# JacdacBreadboardEc30-16x6_128.net
KiCad netlist of a schematic drawn in Altium Designer
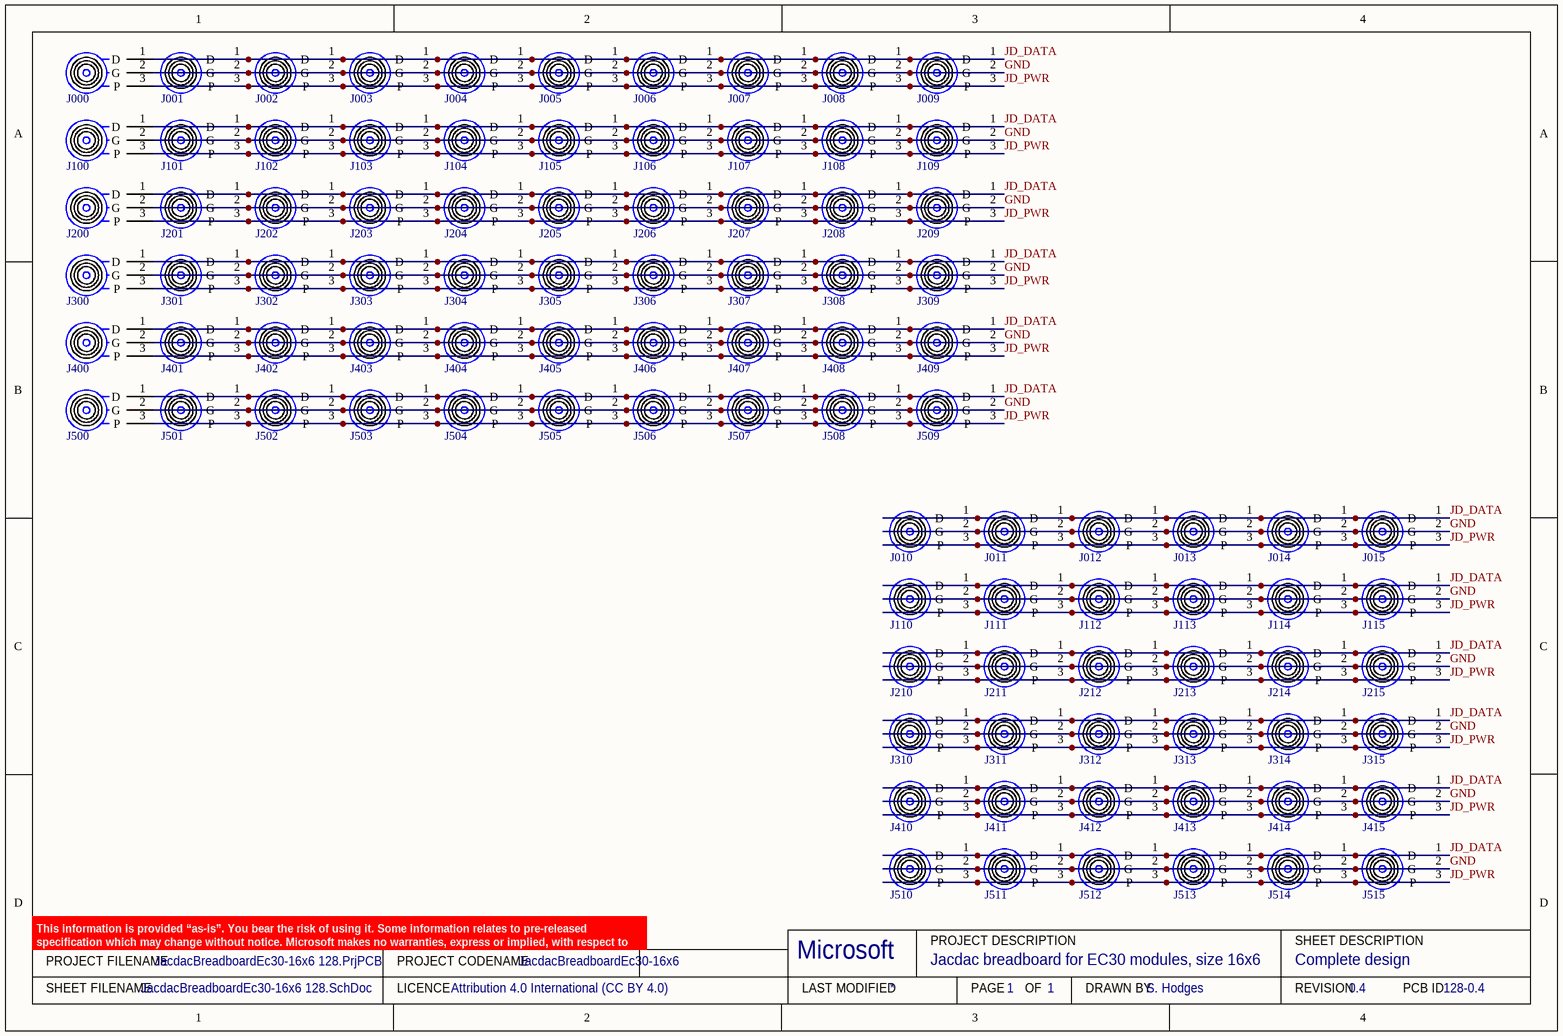
[diagram p0: JacdacBreadboardEc30-16x6 128.SchDoc]

(export (version "E")
  (design (tool "Eeschema 10.0.6"))
  (components
    (comp (ref "J000")
      (value "Jacdac breadboard MH rings")
      (footprint "Jacdac_misc:Jacdac_breadboard_MH_rings_alternative_v5")
      (libsource (lib "generic-con") (part "Jacdac breadboard MH rings"))
    )
    (comp (ref "J001")
      (value "Jacdac breadboard MH rings")
      (footprint "Jacdac_misc:Jacdac_breadboard_MH_rings_alternative_v5")
      (libsource (lib "generic-con") (part "Jacdac breadboard MH rings"))
    )
    (comp (ref "J002")
      (value "Jacdac breadboard MH rings")
      (footprint "Jacdac_misc:Jacdac_breadboard_MH_rings_alternative_v5")
      (libsource (lib "generic-con") (part "Jacdac breadboard MH rings"))
    )
    (comp (ref "J003")
      (value "Jacdac breadboard MH rings")
      (footprint "Jacdac_misc:Jacdac_breadboard_MH_rings_alternative_v5")
      (libsource (lib "generic-con") (part "Jacdac breadboard MH rings"))
    )
    (comp (ref "J004")
      (value "Jacdac breadboard MH rings")
      (footprint "Jacdac_misc:Jacdac_breadboard_MH_rings_alternative_v5")
      (libsource (lib "generic-con") (part "Jacdac breadboard MH rings"))
    )
    (comp (ref "J005")
      (value "Jacdac breadboard MH rings")
      (footprint "Jacdac_misc:Jacdac_breadboard_MH_rings_alternative_v5")
      (libsource (lib "generic-con") (part "Jacdac breadboard MH rings"))
    )
    (comp (ref "J006")
      (value "Jacdac breadboard MH rings")
      (footprint "Jacdac_misc:Jacdac_breadboard_MH_rings_alternative_v5")
      (libsource (lib "generic-con") (part "Jacdac breadboard MH rings"))
    )
    (comp (ref "J007")
      (value "Jacdac breadboard MH rings")
      (footprint "Jacdac_misc:Jacdac_breadboard_MH_rings_alternative_v5")
      (libsource (lib "generic-con") (part "Jacdac breadboard MH rings"))
    )
    (comp (ref "J008")
      (value "Jacdac breadboard MH rings")
      (footprint "Jacdac_misc:Jacdac_breadboard_MH_rings_alternative_v5")
      (libsource (lib "generic-con") (part "Jacdac breadboard MH rings"))
    )
    (comp (ref "J009")
      (value "Jacdac breadboard MH rings")
      (footprint "Jacdac_misc:Jacdac_breadboard_MH_rings_alternative_v5")
      (libsource (lib "generic-con") (part "Jacdac breadboard MH rings"))
    )
    (comp (ref "J010")
      (value "Jacdac breadboard MH rings")
      (footprint "Jacdac_misc:Jacdac_breadboard_MH_rings_alternative_v5")
      (libsource (lib "generic-con") (part "Jacdac breadboard MH rings"))
    )
    (comp (ref "J011")
      (value "Jacdac breadboard MH rings")
      (footprint "Jacdac_misc:Jacdac_breadboard_MH_rings_alternative_v5")
      (libsource (lib "generic-con") (part "Jacdac breadboard MH rings"))
    )
    (comp (ref "J012")
      (value "Jacdac breadboard MH rings")
      (footprint "Jacdac_misc:Jacdac_breadboard_MH_rings_alternative_v5")
      (libsource (lib "generic-con") (part "Jacdac breadboard MH rings"))
    )
    (comp (ref "J013")
      (value "Jacdac breadboard MH rings")
      (footprint "Jacdac_misc:Jacdac_breadboard_MH_rings_alternative_v5")
      (libsource (lib "generic-con") (part "Jacdac breadboard MH rings"))
    )
    (comp (ref "J014")
      (value "Jacdac breadboard MH rings")
      (footprint "Jacdac_misc:Jacdac_breadboard_MH_rings_alternative_v5")
      (libsource (lib "generic-con") (part "Jacdac breadboard MH rings"))
    )
    (comp (ref "J015")
      (value "Jacdac breadboard MH rings")
      (footprint "Jacdac_misc:Jacdac_breadboard_MH_rings_alternative_v5")
      (libsource (lib "generic-con") (part "Jacdac breadboard MH rings"))
    )
    (comp (ref "J100")
      (value "Jacdac breadboard MH rings")
      (footprint "Jacdac_misc:Jacdac_breadboard_MH_rings_alternative_v5")
      (libsource (lib "generic-con") (part "Jacdac breadboard MH rings"))
    )
    (comp (ref "J101")
      (value "Jacdac breadboard MH rings")
      (footprint "Jacdac_misc:Jacdac_breadboard_MH_rings_alternative_v5")
      (libsource (lib "generic-con") (part "Jacdac breadboard MH rings"))
    )
    (comp (ref "J102")
      (value "Jacdac breadboard MH rings")
      (footprint "Jacdac_misc:Jacdac_breadboard_MH_rings_alternative_v5")
      (libsource (lib "generic-con") (part "Jacdac breadboard MH rings"))
    )
    (comp (ref "J103")
      (value "Jacdac breadboard MH rings")
      (footprint "Jacdac_misc:Jacdac_breadboard_MH_rings_alternative_v5")
      (libsource (lib "generic-con") (part "Jacdac breadboard MH rings"))
    )
    (comp (ref "J104")
      (value "Jacdac breadboard MH rings")
      (footprint "Jacdac_misc:Jacdac_breadboard_MH_rings_alternative_v5")
      (libsource (lib "generic-con") (part "Jacdac breadboard MH rings"))
    )
    (comp (ref "J105")
      (value "Jacdac breadboard MH rings")
      (footprint "Jacdac_misc:Jacdac_breadboard_MH_rings_alternative_v5")
      (libsource (lib "generic-con") (part "Jacdac breadboard MH rings"))
    )
    (comp (ref "J106")
      (value "Jacdac breadboard MH rings")
      (footprint "Jacdac_misc:Jacdac_breadboard_MH_rings_alternative_v5")
      (libsource (lib "generic-con") (part "Jacdac breadboard MH rings"))
    )
    (comp (ref "J107")
      (value "Jacdac breadboard MH rings")
      (footprint "Jacdac_misc:Jacdac_breadboard_MH_rings_alternative_v5")
      (libsource (lib "generic-con") (part "Jacdac breadboard MH rings"))
    )
    (comp (ref "J108")
      (value "Jacdac breadboard MH rings")
      (footprint "Jacdac_misc:Jacdac_breadboard_MH_rings_alternative_v5")
      (libsource (lib "generic-con") (part "Jacdac breadboard MH rings"))
    )
    (comp (ref "J109")
      (value "Jacdac breadboard MH rings")
      (footprint "Jacdac_misc:Jacdac_breadboard_MH_rings_alternative_v5")
      (libsource (lib "generic-con") (part "Jacdac breadboard MH rings"))
    )
    (comp (ref "J110")
      (value "Jacdac breadboard MH rings")
      (footprint "Jacdac_misc:Jacdac_breadboard_MH_rings_alternative_v5")
      (libsource (lib "generic-con") (part "Jacdac breadboard MH rings"))
    )
    (comp (ref "J111")
      (value "Jacdac breadboard MH rings")
      (footprint "Jacdac_misc:Jacdac_breadboard_MH_rings_alternative_v5")
      (libsource (lib "generic-con") (part "Jacdac breadboard MH rings"))
    )
    (comp (ref "J112")
      (value "Jacdac breadboard MH rings")
      (footprint "Jacdac_misc:Jacdac_breadboard_MH_rings_alternative_v5")
      (libsource (lib "generic-con") (part "Jacdac breadboard MH rings"))
    )
    (comp (ref "J113")
      (value "Jacdac breadboard MH rings")
      (footprint "Jacdac_misc:Jacdac_breadboard_MH_rings_alternative_v5")
      (libsource (lib "generic-con") (part "Jacdac breadboard MH rings"))
    )
    (comp (ref "J114")
      (value "Jacdac breadboard MH rings")
      (footprint "Jacdac_misc:Jacdac_breadboard_MH_rings_alternative_v5")
      (libsource (lib "generic-con") (part "Jacdac breadboard MH rings"))
    )
    (comp (ref "J115")
      (value "Jacdac breadboard MH rings")
      (footprint "Jacdac_misc:Jacdac_breadboard_MH_rings_alternative_v5")
      (libsource (lib "generic-con") (part "Jacdac breadboard MH rings"))
    )
    (comp (ref "J200")
      (value "Jacdac breadboard MH rings")
      (footprint "Jacdac_misc:Jacdac_breadboard_MH_rings_alternative_v5")
      (libsource (lib "generic-con") (part "Jacdac breadboard MH rings"))
    )
    (comp (ref "J201")
      (value "Jacdac breadboard MH rings")
      (footprint "Jacdac_misc:Jacdac_breadboard_MH_rings_alternative_v5")
      (libsource (lib "generic-con") (part "Jacdac breadboard MH rings"))
    )
    (comp (ref "J202")
      (value "Jacdac breadboard MH rings")
      (footprint "Jacdac_misc:Jacdac_breadboard_MH_rings_alternative_v5")
      (libsource (lib "generic-con") (part "Jacdac breadboard MH rings"))
    )
    (comp (ref "J203")
      (value "Jacdac breadboard MH rings")
      (footprint "Jacdac_misc:Jacdac_breadboard_MH_rings_alternative_v5")
      (libsource (lib "generic-con") (part "Jacdac breadboard MH rings"))
    )
    (comp (ref "J204")
      (value "Jacdac breadboard MH rings")
      (footprint "Jacdac_misc:Jacdac_breadboard_MH_rings_alternative_v5")
      (libsource (lib "generic-con") (part "Jacdac breadboard MH rings"))
    )
    (comp (ref "J205")
      (value "Jacdac breadboard MH rings")
      (footprint "Jacdac_misc:Jacdac_breadboard_MH_rings_alternative_v5")
      (libsource (lib "generic-con") (part "Jacdac breadboard MH rings"))
    )
    (comp (ref "J206")
      (value "Jacdac breadboard MH rings")
      (footprint "Jacdac_misc:Jacdac_breadboard_MH_rings_alternative_v5")
      (libsource (lib "generic-con") (part "Jacdac breadboard MH rings"))
    )
    (comp (ref "J207")
      (value "Jacdac breadboard MH rings")
      (footprint "Jacdac_misc:Jacdac_breadboard_MH_rings_alternative_v5")
      (libsource (lib "generic-con") (part "Jacdac breadboard MH rings"))
    )
    (comp (ref "J208")
      (value "Jacdac breadboard MH rings")
      (footprint "Jacdac_misc:Jacdac_breadboard_MH_rings_alternative_v5")
      (libsource (lib "generic-con") (part "Jacdac breadboard MH rings"))
    )
    (comp (ref "J209")
      (value "Jacdac breadboard MH rings")
      (footprint "Jacdac_misc:Jacdac_breadboard_MH_rings_alternative_v5")
      (libsource (lib "generic-con") (part "Jacdac breadboard MH rings"))
    )
    (comp (ref "J210")
      (value "Jacdac breadboard MH rings")
      (footprint "Jacdac_misc:Jacdac_breadboard_MH_rings_alternative_v5")
      (libsource (lib "generic-con") (part "Jacdac breadboard MH rings"))
    )
    (comp (ref "J211")
      (value "Jacdac breadboard MH rings")
      (footprint "Jacdac_misc:Jacdac_breadboard_MH_rings_alternative_v5")
      (libsource (lib "generic-con") (part "Jacdac breadboard MH rings"))
    )
    (comp (ref "J212")
      (value "Jacdac breadboard MH rings")
      (footprint "Jacdac_misc:Jacdac_breadboard_MH_rings_alternative_v5")
      (libsource (lib "generic-con") (part "Jacdac breadboard MH rings"))
    )
    (comp (ref "J213")
      (value "Jacdac breadboard MH rings")
      (footprint "Jacdac_misc:Jacdac_breadboard_MH_rings_alternative_v5")
      (libsource (lib "generic-con") (part "Jacdac breadboard MH rings"))
    )
    (comp (ref "J214")
      (value "Jacdac breadboard MH rings")
      (footprint "Jacdac_misc:Jacdac_breadboard_MH_rings_alternative_v5")
      (libsource (lib "generic-con") (part "Jacdac breadboard MH rings"))
    )
    (comp (ref "J215")
      (value "Jacdac breadboard MH rings")
      (footprint "Jacdac_misc:Jacdac_breadboard_MH_rings_alternative_v5")
      (libsource (lib "generic-con") (part "Jacdac breadboard MH rings"))
    )
    (comp (ref "J300")
      (value "Jacdac breadboard MH rings")
      (footprint "Jacdac_misc:Jacdac_breadboard_MH_rings_alternative_v5")
      (libsource (lib "generic-con") (part "Jacdac breadboard MH rings"))
    )
    (comp (ref "J301")
      (value "Jacdac breadboard MH rings")
      (footprint "Jacdac_misc:Jacdac_breadboard_MH_rings_alternative_v5")
      (libsource (lib "generic-con") (part "Jacdac breadboard MH rings"))
    )
    (comp (ref "J302")
      (value "Jacdac breadboard MH rings")
      (footprint "Jacdac_misc:Jacdac_breadboard_MH_rings_alternative_v5")
      (libsource (lib "generic-con") (part "Jacdac breadboard MH rings"))
    )
    (comp (ref "J303")
      (value "Jacdac breadboard MH rings")
      (footprint "Jacdac_misc:Jacdac_breadboard_MH_rings_alternative_v5")
      (libsource (lib "generic-con") (part "Jacdac breadboard MH rings"))
    )
    (comp (ref "J304")
      (value "Jacdac breadboard MH rings")
      (footprint "Jacdac_misc:Jacdac_breadboard_MH_rings_alternative_v5")
      (libsource (lib "generic-con") (part "Jacdac breadboard MH rings"))
    )
    (comp (ref "J305")
      (value "Jacdac breadboard MH rings")
      (footprint "Jacdac_misc:Jacdac_breadboard_MH_rings_alternative_v5")
      (libsource (lib "generic-con") (part "Jacdac breadboard MH rings"))
    )
    (comp (ref "J306")
      (value "Jacdac breadboard MH rings")
      (footprint "Jacdac_misc:Jacdac_breadboard_MH_rings_alternative_v5")
      (libsource (lib "generic-con") (part "Jacdac breadboard MH rings"))
    )
    (comp (ref "J307")
      (value "Jacdac breadboard MH rings")
      (footprint "Jacdac_misc:Jacdac_breadboard_MH_rings_alternative_v5")
      (libsource (lib "generic-con") (part "Jacdac breadboard MH rings"))
    )
    (comp (ref "J308")
      (value "Jacdac breadboard MH rings")
      (footprint "Jacdac_misc:Jacdac_breadboard_MH_rings_alternative_v5")
      (libsource (lib "generic-con") (part "Jacdac breadboard MH rings"))
    )
    (comp (ref "J309")
      (value "Jacdac breadboard MH rings")
      (footprint "Jacdac_misc:Jacdac_breadboard_MH_rings_alternative_v5")
      (libsource (lib "generic-con") (part "Jacdac breadboard MH rings"))
    )
    (comp (ref "J310")
      (value "Jacdac breadboard MH rings")
      (footprint "Jacdac_misc:Jacdac_breadboard_MH_rings_alternative_v5")
      (libsource (lib "generic-con") (part "Jacdac breadboard MH rings"))
    )
    (comp (ref "J311")
      (value "Jacdac breadboard MH rings")
      (footprint "Jacdac_misc:Jacdac_breadboard_MH_rings_alternative_v5")
      (libsource (lib "generic-con") (part "Jacdac breadboard MH rings"))
    )
    (comp (ref "J312")
      (value "Jacdac breadboard MH rings")
      (footprint "Jacdac_misc:Jacdac_breadboard_MH_rings_alternative_v5")
      (libsource (lib "generic-con") (part "Jacdac breadboard MH rings"))
    )
    (comp (ref "J313")
      (value "Jacdac breadboard MH rings")
      (footprint "Jacdac_misc:Jacdac_breadboard_MH_rings_alternative_v5")
      (libsource (lib "generic-con") (part "Jacdac breadboard MH rings"))
    )
    (comp (ref "J314")
      (value "Jacdac breadboard MH rings")
      (footprint "Jacdac_misc:Jacdac_breadboard_MH_rings_alternative_v5")
      (libsource (lib "generic-con") (part "Jacdac breadboard MH rings"))
    )
    (comp (ref "J315")
      (value "Jacdac breadboard MH rings")
      (footprint "Jacdac_misc:Jacdac_breadboard_MH_rings_alternative_v5")
      (libsource (lib "generic-con") (part "Jacdac breadboard MH rings"))
    )
    (comp (ref "J400")
      (value "Jacdac breadboard MH rings")
      (footprint "Jacdac_misc:Jacdac_breadboard_MH_rings_alternative_v5")
      (libsource (lib "generic-con") (part "Jacdac breadboard MH rings"))
    )
    (comp (ref "J401")
      (value "Jacdac breadboard MH rings")
      (footprint "Jacdac_misc:Jacdac_breadboard_MH_rings_alternative_v5")
      (libsource (lib "generic-con") (part "Jacdac breadboard MH rings"))
    )
    (comp (ref "J402")
      (value "Jacdac breadboard MH rings")
      (footprint "Jacdac_misc:Jacdac_breadboard_MH_rings_alternative_v5")
      (libsource (lib "generic-con") (part "Jacdac breadboard MH rings"))
    )
    (comp (ref "J403")
      (value "Jacdac breadboard MH rings")
      (footprint "Jacdac_misc:Jacdac_breadboard_MH_rings_alternative_v5")
      (libsource (lib "generic-con") (part "Jacdac breadboard MH rings"))
    )
    (comp (ref "J404")
      (value "Jacdac breadboard MH rings")
      (footprint "Jacdac_misc:Jacdac_breadboard_MH_rings_alternative_v5")
      (libsource (lib "generic-con") (part "Jacdac breadboard MH rings"))
    )
    (comp (ref "J405")
      (value "Jacdac breadboard MH rings")
      (footprint "Jacdac_misc:Jacdac_breadboard_MH_rings_alternative_v5")
      (libsource (lib "generic-con") (part "Jacdac breadboard MH rings"))
    )
    (comp (ref "J406")
      (value "Jacdac breadboard MH rings")
      (footprint "Jacdac_misc:Jacdac_breadboard_MH_rings_alternative_v5")
      (libsource (lib "generic-con") (part "Jacdac breadboard MH rings"))
    )
    (comp (ref "J407")
      (value "Jacdac breadboard MH rings")
      (footprint "Jacdac_misc:Jacdac_breadboard_MH_rings_alternative_v5")
      (libsource (lib "generic-con") (part "Jacdac breadboard MH rings"))
    )
    (comp (ref "J408")
      (value "Jacdac breadboard MH rings")
      (footprint "Jacdac_misc:Jacdac_breadboard_MH_rings_alternative_v5")
      (libsource (lib "generic-con") (part "Jacdac breadboard MH rings"))
    )
    (comp (ref "J409")
      (value "Jacdac breadboard MH rings")
      (footprint "Jacdac_misc:Jacdac_breadboard_MH_rings_alternative_v5")
      (libsource (lib "generic-con") (part "Jacdac breadboard MH rings"))
    )
    (comp (ref "J410")
      (value "Jacdac breadboard MH rings")
      (footprint "Jacdac_misc:Jacdac_breadboard_MH_rings_alternative_v5")
      (libsource (lib "generic-con") (part "Jacdac breadboard MH rings"))
    )
    (comp (ref "J411")
      (value "Jacdac breadboard MH rings")
      (footprint "Jacdac_misc:Jacdac_breadboard_MH_rings_alternative_v5")
      (libsource (lib "generic-con") (part "Jacdac breadboard MH rings"))
    )
    (comp (ref "J412")
      (value "Jacdac breadboard MH rings")
      (footprint "Jacdac_misc:Jacdac_breadboard_MH_rings_alternative_v5")
      (libsource (lib "generic-con") (part "Jacdac breadboard MH rings"))
    )
    (comp (ref "J413")
      (value "Jacdac breadboard MH rings")
      (footprint "Jacdac_misc:Jacdac_breadboard_MH_rings_alternative_v5")
      (libsource (lib "generic-con") (part "Jacdac breadboard MH rings"))
    )
    (comp (ref "J414")
      (value "Jacdac breadboard MH rings")
      (footprint "Jacdac_misc:Jacdac_breadboard_MH_rings_alternative_v5")
      (libsource (lib "generic-con") (part "Jacdac breadboard MH rings"))
    )
    (comp (ref "J415")
      (value "Jacdac breadboard MH rings")
      (footprint "Jacdac_misc:Jacdac_breadboard_MH_rings_alternative_v5")
      (libsource (lib "generic-con") (part "Jacdac breadboard MH rings"))
    )
    (comp (ref "J500")
      (value "Jacdac breadboard MH rings")
      (footprint "Jacdac_misc:Jacdac_breadboard_MH_rings_alternative_v5")
      (libsource (lib "generic-con") (part "Jacdac breadboard MH rings"))
    )
    (comp (ref "J501")
      (value "Jacdac breadboard MH rings")
      (footprint "Jacdac_misc:Jacdac_breadboard_MH_rings_alternative_v5")
      (libsource (lib "generic-con") (part "Jacdac breadboard MH rings"))
    )
    (comp (ref "J502")
      (value "Jacdac breadboard MH rings")
      (footprint "Jacdac_misc:Jacdac_breadboard_MH_rings_alternative_v5")
      (libsource (lib "generic-con") (part "Jacdac breadboard MH rings"))
    )
    (comp (ref "J503")
      (value "Jacdac breadboard MH rings")
      (footprint "Jacdac_misc:Jacdac_breadboard_MH_rings_alternative_v5")
      (libsource (lib "generic-con") (part "Jacdac breadboard MH rings"))
    )
    (comp (ref "J504")
      (value "Jacdac breadboard MH rings")
      (footprint "Jacdac_misc:Jacdac_breadboard_MH_rings_alternative_v5")
      (libsource (lib "generic-con") (part "Jacdac breadboard MH rings"))
    )
    (comp (ref "J505")
      (value "Jacdac breadboard MH rings")
      (footprint "Jacdac_misc:Jacdac_breadboard_MH_rings_alternative_v5")
      (libsource (lib "generic-con") (part "Jacdac breadboard MH rings"))
    )
    (comp (ref "J506")
      (value "Jacdac breadboard MH rings")
      (footprint "Jacdac_misc:Jacdac_breadboard_MH_rings_alternative_v5")
      (libsource (lib "generic-con") (part "Jacdac breadboard MH rings"))
    )
    (comp (ref "J507")
      (value "Jacdac breadboard MH rings")
      (footprint "Jacdac_misc:Jacdac_breadboard_MH_rings_alternative_v5")
      (libsource (lib "generic-con") (part "Jacdac breadboard MH rings"))
    )
    (comp (ref "J508")
      (value "Jacdac breadboard MH rings")
      (footprint "Jacdac_misc:Jacdac_breadboard_MH_rings_alternative_v5")
      (libsource (lib "generic-con") (part "Jacdac breadboard MH rings"))
    )
    (comp (ref "J509")
      (value "Jacdac breadboard MH rings")
      (footprint "Jacdac_misc:Jacdac_breadboard_MH_rings_alternative_v5")
      (libsource (lib "generic-con") (part "Jacdac breadboard MH rings"))
    )
    (comp (ref "J510")
      (value "Jacdac breadboard MH rings")
      (footprint "Jacdac_misc:Jacdac_breadboard_MH_rings_alternative_v5")
      (libsource (lib "generic-con") (part "Jacdac breadboard MH rings"))
    )
    (comp (ref "J511")
      (value "Jacdac breadboard MH rings")
      (footprint "Jacdac_misc:Jacdac_breadboard_MH_rings_alternative_v5")
      (libsource (lib "generic-con") (part "Jacdac breadboard MH rings"))
    )
    (comp (ref "J512")
      (value "Jacdac breadboard MH rings")
      (footprint "Jacdac_misc:Jacdac_breadboard_MH_rings_alternative_v5")
      (libsource (lib "generic-con") (part "Jacdac breadboard MH rings"))
    )
    (comp (ref "J513")
      (value "Jacdac breadboard MH rings")
      (footprint "Jacdac_misc:Jacdac_breadboard_MH_rings_alternative_v5")
      (libsource (lib "generic-con") (part "Jacdac breadboard MH rings"))
    )
    (comp (ref "J514")
      (value "Jacdac breadboard MH rings")
      (footprint "Jacdac_misc:Jacdac_breadboard_MH_rings_alternative_v5")
      (libsource (lib "generic-con") (part "Jacdac breadboard MH rings"))
    )
    (comp (ref "J515")
      (value "Jacdac breadboard MH rings")
      (footprint "Jacdac_misc:Jacdac_breadboard_MH_rings_alternative_v5")
      (libsource (lib "generic-con") (part "Jacdac breadboard MH rings"))
    )
  )
  (nets
    (net (code "1") (name "/GND") (class "Default")
      (node (ref "J000") (pin "2") (pinfunction "G_2") (pintype "passive"))
      (node (ref "J001") (pin "2") (pinfunction "G_2") (pintype "passive"))
      (node (ref "J002") (pin "2") (pinfunction "G_2") (pintype "passive"))
      (node (ref "J003") (pin "2") (pinfunction "G_2") (pintype "passive"))
      (node (ref "J004") (pin "2") (pinfunction "G_2") (pintype "passive"))
      (node (ref "J005") (pin "2") (pinfunction "G_2") (pintype "passive"))
      (node (ref "J006") (pin "2") (pinfunction "G_2") (pintype "passive"))
      (node (ref "J007") (pin "2") (pinfunction "G_2") (pintype "passive"))
      (node (ref "J008") (pin "2") (pinfunction "G_2") (pintype "passive"))
      (node (ref "J009") (pin "2") (pinfunction "G_2") (pintype "passive"))
      (node (ref "J010") (pin "2") (pinfunction "G_2") (pintype "passive"))
      (node (ref "J011") (pin "2") (pinfunction "G_2") (pintype "passive"))
      (node (ref "J012") (pin "2") (pinfunction "G_2") (pintype "passive"))
      (node (ref "J013") (pin "2") (pinfunction "G_2") (pintype "passive"))
      (node (ref "J014") (pin "2") (pinfunction "G_2") (pintype "passive"))
      (node (ref "J015") (pin "2") (pinfunction "G_2") (pintype "passive"))
      (node (ref "J100") (pin "2") (pinfunction "G_2") (pintype "passive"))
      (node (ref "J101") (pin "2") (pinfunction "G_2") (pintype "passive"))
      (node (ref "J102") (pin "2") (pinfunction "G_2") (pintype "passive"))
      (node (ref "J103") (pin "2") (pinfunction "G_2") (pintype "passive"))
      (node (ref "J104") (pin "2") (pinfunction "G_2") (pintype "passive"))
      (node (ref "J105") (pin "2") (pinfunction "G_2") (pintype "passive"))
      (node (ref "J106") (pin "2") (pinfunction "G_2") (pintype "passive"))
      (node (ref "J107") (pin "2") (pinfunction "G_2") (pintype "passive"))
      (node (ref "J108") (pin "2") (pinfunction "G_2") (pintype "passive"))
      (node (ref "J109") (pin "2") (pinfunction "G_2") (pintype "passive"))
      (node (ref "J110") (pin "2") (pinfunction "G_2") (pintype "passive"))
      (node (ref "J111") (pin "2") (pinfunction "G_2") (pintype "passive"))
      (node (ref "J112") (pin "2") (pinfunction "G_2") (pintype "passive"))
      (node (ref "J113") (pin "2") (pinfunction "G_2") (pintype "passive"))
      (node (ref "J114") (pin "2") (pinfunction "G_2") (pintype "passive"))
      (node (ref "J115") (pin "2") (pinfunction "G_2") (pintype "passive"))
      (node (ref "J200") (pin "2") (pinfunction "G_2") (pintype "passive"))
      (node (ref "J201") (pin "2") (pinfunction "G_2") (pintype "passive"))
      (node (ref "J202") (pin "2") (pinfunction "G_2") (pintype "passive"))
      (node (ref "J203") (pin "2") (pinfunction "G_2") (pintype "passive"))
      (node (ref "J204") (pin "2") (pinfunction "G_2") (pintype "passive"))
      (node (ref "J205") (pin "2") (pinfunction "G_2") (pintype "passive"))
      (node (ref "J206") (pin "2") (pinfunction "G_2") (pintype "passive"))
      (node (ref "J207") (pin "2") (pinfunction "G_2") (pintype "passive"))
      (node (ref "J208") (pin "2") (pinfunction "G_2") (pintype "passive"))
      (node (ref "J209") (pin "2") (pinfunction "G_2") (pintype "passive"))
      (node (ref "J210") (pin "2") (pinfunction "G_2") (pintype "passive"))
      (node (ref "J211") (pin "2") (pinfunction "G_2") (pintype "passive"))
      (node (ref "J212") (pin "2") (pinfunction "G_2") (pintype "passive"))
      (node (ref "J213") (pin "2") (pinfunction "G_2") (pintype "passive"))
      (node (ref "J214") (pin "2") (pinfunction "G_2") (pintype "passive"))
      (node (ref "J215") (pin "2") (pinfunction "G_2") (pintype "passive"))
      (node (ref "J300") (pin "2") (pinfunction "G_2") (pintype "passive"))
      (node (ref "J301") (pin "2") (pinfunction "G_2") (pintype "passive"))
      (node (ref "J302") (pin "2") (pinfunction "G_2") (pintype "passive"))
      (node (ref "J303") (pin "2") (pinfunction "G_2") (pintype "passive"))
      (node (ref "J304") (pin "2") (pinfunction "G_2") (pintype "passive"))
      (node (ref "J305") (pin "2") (pinfunction "G_2") (pintype "passive"))
      (node (ref "J306") (pin "2") (pinfunction "G_2") (pintype "passive"))
      (node (ref "J307") (pin "2") (pinfunction "G_2") (pintype "passive"))
      (node (ref "J308") (pin "2") (pinfunction "G_2") (pintype "passive"))
      (node (ref "J309") (pin "2") (pinfunction "G_2") (pintype "passive"))
      (node (ref "J310") (pin "2") (pinfunction "G_2") (pintype "passive"))
      (node (ref "J311") (pin "2") (pinfunction "G_2") (pintype "passive"))
      (node (ref "J312") (pin "2") (pinfunction "G_2") (pintype "passive"))
      (node (ref "J313") (pin "2") (pinfunction "G_2") (pintype "passive"))
      (node (ref "J314") (pin "2") (pinfunction "G_2") (pintype "passive"))
      (node (ref "J315") (pin "2") (pinfunction "G_2") (pintype "passive"))
      (node (ref "J400") (pin "2") (pinfunction "G_2") (pintype "passive"))
      (node (ref "J401") (pin "2") (pinfunction "G_2") (pintype "passive"))
      (node (ref "J402") (pin "2") (pinfunction "G_2") (pintype "passive"))
      (node (ref "J403") (pin "2") (pinfunction "G_2") (pintype "passive"))
      (node (ref "J404") (pin "2") (pinfunction "G_2") (pintype "passive"))
      (node (ref "J405") (pin "2") (pinfunction "G_2") (pintype "passive"))
      (node (ref "J406") (pin "2") (pinfunction "G_2") (pintype "passive"))
      (node (ref "J407") (pin "2") (pinfunction "G_2") (pintype "passive"))
      (node (ref "J408") (pin "2") (pinfunction "G_2") (pintype "passive"))
      (node (ref "J409") (pin "2") (pinfunction "G_2") (pintype "passive"))
      (node (ref "J410") (pin "2") (pinfunction "G_2") (pintype "passive"))
      (node (ref "J411") (pin "2") (pinfunction "G_2") (pintype "passive"))
      (node (ref "J412") (pin "2") (pinfunction "G_2") (pintype "passive"))
      (node (ref "J413") (pin "2") (pinfunction "G_2") (pintype "passive"))
      (node (ref "J414") (pin "2") (pinfunction "G_2") (pintype "passive"))
      (node (ref "J415") (pin "2") (pinfunction "G_2") (pintype "passive"))
      (node (ref "J500") (pin "2") (pinfunction "G_2") (pintype "passive"))
      (node (ref "J501") (pin "2") (pinfunction "G_2") (pintype "passive"))
      (node (ref "J502") (pin "2") (pinfunction "G_2") (pintype "passive"))
      (node (ref "J503") (pin "2") (pinfunction "G_2") (pintype "passive"))
      (node (ref "J504") (pin "2") (pinfunction "G_2") (pintype "passive"))
      (node (ref "J505") (pin "2") (pinfunction "G_2") (pintype "passive"))
      (node (ref "J506") (pin "2") (pinfunction "G_2") (pintype "passive"))
      (node (ref "J507") (pin "2") (pinfunction "G_2") (pintype "passive"))
      (node (ref "J508") (pin "2") (pinfunction "G_2") (pintype "passive"))
      (node (ref "J509") (pin "2") (pinfunction "G_2") (pintype "passive"))
      (node (ref "J510") (pin "2") (pinfunction "G_2") (pintype "passive"))
      (node (ref "J511") (pin "2") (pinfunction "G_2") (pintype "passive"))
      (node (ref "J512") (pin "2") (pinfunction "G_2") (pintype "passive"))
      (node (ref "J513") (pin "2") (pinfunction "G_2") (pintype "passive"))
      (node (ref "J514") (pin "2") (pinfunction "G_2") (pintype "passive"))
      (node (ref "J515") (pin "2") (pinfunction "G_2") (pintype "passive"))
    )
    (net (code "2") (name "/JD_DATA") (class "Default")
      (node (ref "J000") (pin "1") (pinfunction "D_1") (pintype "passive"))
      (node (ref "J001") (pin "1") (pinfunction "D_1") (pintype "passive"))
      (node (ref "J002") (pin "1") (pinfunction "D_1") (pintype "passive"))
      (node (ref "J003") (pin "1") (pinfunction "D_1") (pintype "passive"))
      (node (ref "J004") (pin "1") (pinfunction "D_1") (pintype "passive"))
      (node (ref "J005") (pin "1") (pinfunction "D_1") (pintype "passive"))
      (node (ref "J006") (pin "1") (pinfunction "D_1") (pintype "passive"))
      (node (ref "J007") (pin "1") (pinfunction "D_1") (pintype "passive"))
      (node (ref "J008") (pin "1") (pinfunction "D_1") (pintype "passive"))
      (node (ref "J009") (pin "1") (pinfunction "D_1") (pintype "passive"))
      (node (ref "J010") (pin "1") (pinfunction "D_1") (pintype "passive"))
      (node (ref "J011") (pin "1") (pinfunction "D_1") (pintype "passive"))
      (node (ref "J012") (pin "1") (pinfunction "D_1") (pintype "passive"))
      (node (ref "J013") (pin "1") (pinfunction "D_1") (pintype "passive"))
      (node (ref "J014") (pin "1") (pinfunction "D_1") (pintype "passive"))
      (node (ref "J015") (pin "1") (pinfunction "D_1") (pintype "passive"))
      (node (ref "J100") (pin "1") (pinfunction "D_1") (pintype "passive"))
      (node (ref "J101") (pin "1") (pinfunction "D_1") (pintype "passive"))
      (node (ref "J102") (pin "1") (pinfunction "D_1") (pintype "passive"))
      (node (ref "J103") (pin "1") (pinfunction "D_1") (pintype "passive"))
      (node (ref "J104") (pin "1") (pinfunction "D_1") (pintype "passive"))
      (node (ref "J105") (pin "1") (pinfunction "D_1") (pintype "passive"))
      (node (ref "J106") (pin "1") (pinfunction "D_1") (pintype "passive"))
      (node (ref "J107") (pin "1") (pinfunction "D_1") (pintype "passive"))
      (node (ref "J108") (pin "1") (pinfunction "D_1") (pintype "passive"))
      (node (ref "J109") (pin "1") (pinfunction "D_1") (pintype "passive"))
      (node (ref "J110") (pin "1") (pinfunction "D_1") (pintype "passive"))
      (node (ref "J111") (pin "1") (pinfunction "D_1") (pintype "passive"))
      (node (ref "J112") (pin "1") (pinfunction "D_1") (pintype "passive"))
      (node (ref "J113") (pin "1") (pinfunction "D_1") (pintype "passive"))
      (node (ref "J114") (pin "1") (pinfunction "D_1") (pintype "passive"))
      (node (ref "J115") (pin "1") (pinfunction "D_1") (pintype "passive"))
      (node (ref "J200") (pin "1") (pinfunction "D_1") (pintype "passive"))
      (node (ref "J201") (pin "1") (pinfunction "D_1") (pintype "passive"))
      (node (ref "J202") (pin "1") (pinfunction "D_1") (pintype "passive"))
      (node (ref "J203") (pin "1") (pinfunction "D_1") (pintype "passive"))
      (node (ref "J204") (pin "1") (pinfunction "D_1") (pintype "passive"))
      (node (ref "J205") (pin "1") (pinfunction "D_1") (pintype "passive"))
      (node (ref "J206") (pin "1") (pinfunction "D_1") (pintype "passive"))
      (node (ref "J207") (pin "1") (pinfunction "D_1") (pintype "passive"))
      (node (ref "J208") (pin "1") (pinfunction "D_1") (pintype "passive"))
      (node (ref "J209") (pin "1") (pinfunction "D_1") (pintype "passive"))
      (node (ref "J210") (pin "1") (pinfunction "D_1") (pintype "passive"))
      (node (ref "J211") (pin "1") (pinfunction "D_1") (pintype "passive"))
      (node (ref "J212") (pin "1") (pinfunction "D_1") (pintype "passive"))
      (node (ref "J213") (pin "1") (pinfunction "D_1") (pintype "passive"))
      (node (ref "J214") (pin "1") (pinfunction "D_1") (pintype "passive"))
      (node (ref "J215") (pin "1") (pinfunction "D_1") (pintype "passive"))
      (node (ref "J300") (pin "1") (pinfunction "D_1") (pintype "passive"))
      (node (ref "J301") (pin "1") (pinfunction "D_1") (pintype "passive"))
      (node (ref "J302") (pin "1") (pinfunction "D_1") (pintype "passive"))
      (node (ref "J303") (pin "1") (pinfunction "D_1") (pintype "passive"))
      (node (ref "J304") (pin "1") (pinfunction "D_1") (pintype "passive"))
      (node (ref "J305") (pin "1") (pinfunction "D_1") (pintype "passive"))
      (node (ref "J306") (pin "1") (pinfunction "D_1") (pintype "passive"))
      (node (ref "J307") (pin "1") (pinfunction "D_1") (pintype "passive"))
      (node (ref "J308") (pin "1") (pinfunction "D_1") (pintype "passive"))
      (node (ref "J309") (pin "1") (pinfunction "D_1") (pintype "passive"))
      (node (ref "J310") (pin "1") (pinfunction "D_1") (pintype "passive"))
      (node (ref "J311") (pin "1") (pinfunction "D_1") (pintype "passive"))
      (node (ref "J312") (pin "1") (pinfunction "D_1") (pintype "passive"))
      (node (ref "J313") (pin "1") (pinfunction "D_1") (pintype "passive"))
      (node (ref "J314") (pin "1") (pinfunction "D_1") (pintype "passive"))
      (node (ref "J315") (pin "1") (pinfunction "D_1") (pintype "passive"))
      (node (ref "J400") (pin "1") (pinfunction "D_1") (pintype "passive"))
      (node (ref "J401") (pin "1") (pinfunction "D_1") (pintype "passive"))
      (node (ref "J402") (pin "1") (pinfunction "D_1") (pintype "passive"))
      (node (ref "J403") (pin "1") (pinfunction "D_1") (pintype "passive"))
      (node (ref "J404") (pin "1") (pinfunction "D_1") (pintype "passive"))
      (node (ref "J405") (pin "1") (pinfunction "D_1") (pintype "passive"))
      (node (ref "J406") (pin "1") (pinfunction "D_1") (pintype "passive"))
      (node (ref "J407") (pin "1") (pinfunction "D_1") (pintype "passive"))
      (node (ref "J408") (pin "1") (pinfunction "D_1") (pintype "passive"))
      (node (ref "J409") (pin "1") (pinfunction "D_1") (pintype "passive"))
      (node (ref "J410") (pin "1") (pinfunction "D_1") (pintype "passive"))
      (node (ref "J411") (pin "1") (pinfunction "D_1") (pintype "passive"))
      (node (ref "J412") (pin "1") (pinfunction "D_1") (pintype "passive"))
      (node (ref "J413") (pin "1") (pinfunction "D_1") (pintype "passive"))
      (node (ref "J414") (pin "1") (pinfunction "D_1") (pintype "passive"))
      (node (ref "J415") (pin "1") (pinfunction "D_1") (pintype "passive"))
      (node (ref "J500") (pin "1") (pinfunction "D_1") (pintype "passive"))
      (node (ref "J501") (pin "1") (pinfunction "D_1") (pintype "passive"))
      (node (ref "J502") (pin "1") (pinfunction "D_1") (pintype "passive"))
      (node (ref "J503") (pin "1") (pinfunction "D_1") (pintype "passive"))
      (node (ref "J504") (pin "1") (pinfunction "D_1") (pintype "passive"))
      (node (ref "J505") (pin "1") (pinfunction "D_1") (pintype "passive"))
      (node (ref "J506") (pin "1") (pinfunction "D_1") (pintype "passive"))
      (node (ref "J507") (pin "1") (pinfunction "D_1") (pintype "passive"))
      (node (ref "J508") (pin "1") (pinfunction "D_1") (pintype "passive"))
      (node (ref "J509") (pin "1") (pinfunction "D_1") (pintype "passive"))
      (node (ref "J510") (pin "1") (pinfunction "D_1") (pintype "passive"))
      (node (ref "J511") (pin "1") (pinfunction "D_1") (pintype "passive"))
      (node (ref "J512") (pin "1") (pinfunction "D_1") (pintype "passive"))
      (node (ref "J513") (pin "1") (pinfunction "D_1") (pintype "passive"))
      (node (ref "J514") (pin "1") (pinfunction "D_1") (pintype "passive"))
      (node (ref "J515") (pin "1") (pinfunction "D_1") (pintype "passive"))
    )
    (net (code "3") (name "/JD_PWR") (class "Default")
      (node (ref "J000") (pin "3") (pinfunction "P_3") (pintype "passive"))
      (node (ref "J001") (pin "3") (pinfunction "P_3") (pintype "passive"))
      (node (ref "J002") (pin "3") (pinfunction "P_3") (pintype "passive"))
      (node (ref "J003") (pin "3") (pinfunction "P_3") (pintype "passive"))
      (node (ref "J004") (pin "3") (pinfunction "P_3") (pintype "passive"))
      (node (ref "J005") (pin "3") (pinfunction "P_3") (pintype "passive"))
      (node (ref "J006") (pin "3") (pinfunction "P_3") (pintype "passive"))
      (node (ref "J007") (pin "3") (pinfunction "P_3") (pintype "passive"))
      (node (ref "J008") (pin "3") (pinfunction "P_3") (pintype "passive"))
      (node (ref "J009") (pin "3") (pinfunction "P_3") (pintype "passive"))
      (node (ref "J010") (pin "3") (pinfunction "P_3") (pintype "passive"))
      (node (ref "J011") (pin "3") (pinfunction "P_3") (pintype "passive"))
      (node (ref "J012") (pin "3") (pinfunction "P_3") (pintype "passive"))
      (node (ref "J013") (pin "3") (pinfunction "P_3") (pintype "passive"))
      (node (ref "J014") (pin "3") (pinfunction "P_3") (pintype "passive"))
      (node (ref "J015") (pin "3") (pinfunction "P_3") (pintype "passive"))
      (node (ref "J100") (pin "3") (pinfunction "P_3") (pintype "passive"))
      (node (ref "J101") (pin "3") (pinfunction "P_3") (pintype "passive"))
      (node (ref "J102") (pin "3") (pinfunction "P_3") (pintype "passive"))
      (node (ref "J103") (pin "3") (pinfunction "P_3") (pintype "passive"))
      (node (ref "J104") (pin "3") (pinfunction "P_3") (pintype "passive"))
      (node (ref "J105") (pin "3") (pinfunction "P_3") (pintype "passive"))
      (node (ref "J106") (pin "3") (pinfunction "P_3") (pintype "passive"))
      (node (ref "J107") (pin "3") (pinfunction "P_3") (pintype "passive"))
      (node (ref "J108") (pin "3") (pinfunction "P_3") (pintype "passive"))
      (node (ref "J109") (pin "3") (pinfunction "P_3") (pintype "passive"))
      (node (ref "J110") (pin "3") (pinfunction "P_3") (pintype "passive"))
      (node (ref "J111") (pin "3") (pinfunction "P_3") (pintype "passive"))
      (node (ref "J112") (pin "3") (pinfunction "P_3") (pintype "passive"))
      (node (ref "J113") (pin "3") (pinfunction "P_3") (pintype "passive"))
      (node (ref "J114") (pin "3") (pinfunction "P_3") (pintype "passive"))
      (node (ref "J115") (pin "3") (pinfunction "P_3") (pintype "passive"))
      (node (ref "J200") (pin "3") (pinfunction "P_3") (pintype "passive"))
      (node (ref "J201") (pin "3") (pinfunction "P_3") (pintype "passive"))
      (node (ref "J202") (pin "3") (pinfunction "P_3") (pintype "passive"))
      (node (ref "J203") (pin "3") (pinfunction "P_3") (pintype "passive"))
      (node (ref "J204") (pin "3") (pinfunction "P_3") (pintype "passive"))
      (node (ref "J205") (pin "3") (pinfunction "P_3") (pintype "passive"))
      (node (ref "J206") (pin "3") (pinfunction "P_3") (pintype "passive"))
      (node (ref "J207") (pin "3") (pinfunction "P_3") (pintype "passive"))
      (node (ref "J208") (pin "3") (pinfunction "P_3") (pintype "passive"))
      (node (ref "J209") (pin "3") (pinfunction "P_3") (pintype "passive"))
      (node (ref "J210") (pin "3") (pinfunction "P_3") (pintype "passive"))
      (node (ref "J211") (pin "3") (pinfunction "P_3") (pintype "passive"))
      (node (ref "J212") (pin "3") (pinfunction "P_3") (pintype "passive"))
      (node (ref "J213") (pin "3") (pinfunction "P_3") (pintype "passive"))
      (node (ref "J214") (pin "3") (pinfunction "P_3") (pintype "passive"))
      (node (ref "J215") (pin "3") (pinfunction "P_3") (pintype "passive"))
      (node (ref "J300") (pin "3") (pinfunction "P_3") (pintype "passive"))
      (node (ref "J301") (pin "3") (pinfunction "P_3") (pintype "passive"))
      (node (ref "J302") (pin "3") (pinfunction "P_3") (pintype "passive"))
      (node (ref "J303") (pin "3") (pinfunction "P_3") (pintype "passive"))
      (node (ref "J304") (pin "3") (pinfunction "P_3") (pintype "passive"))
      (node (ref "J305") (pin "3") (pinfunction "P_3") (pintype "passive"))
      (node (ref "J306") (pin "3") (pinfunction "P_3") (pintype "passive"))
      (node (ref "J307") (pin "3") (pinfunction "P_3") (pintype "passive"))
      (node (ref "J308") (pin "3") (pinfunction "P_3") (pintype "passive"))
      (node (ref "J309") (pin "3") (pinfunction "P_3") (pintype "passive"))
      (node (ref "J310") (pin "3") (pinfunction "P_3") (pintype "passive"))
      (node (ref "J311") (pin "3") (pinfunction "P_3") (pintype "passive"))
      (node (ref "J312") (pin "3") (pinfunction "P_3") (pintype "passive"))
      (node (ref "J313") (pin "3") (pinfunction "P_3") (pintype "passive"))
      (node (ref "J314") (pin "3") (pinfunction "P_3") (pintype "passive"))
      (node (ref "J315") (pin "3") (pinfunction "P_3") (pintype "passive"))
      (node (ref "J400") (pin "3") (pinfunction "P_3") (pintype "passive"))
      (node (ref "J401") (pin "3") (pinfunction "P_3") (pintype "passive"))
      (node (ref "J402") (pin "3") (pinfunction "P_3") (pintype "passive"))
      (node (ref "J403") (pin "3") (pinfunction "P_3") (pintype "passive"))
      (node (ref "J404") (pin "3") (pinfunction "P_3") (pintype "passive"))
      (node (ref "J405") (pin "3") (pinfunction "P_3") (pintype "passive"))
      (node (ref "J406") (pin "3") (pinfunction "P_3") (pintype "passive"))
      (node (ref "J407") (pin "3") (pinfunction "P_3") (pintype "passive"))
      (node (ref "J408") (pin "3") (pinfunction "P_3") (pintype "passive"))
      (node (ref "J409") (pin "3") (pinfunction "P_3") (pintype "passive"))
      (node (ref "J410") (pin "3") (pinfunction "P_3") (pintype "passive"))
      (node (ref "J411") (pin "3") (pinfunction "P_3") (pintype "passive"))
      (node (ref "J412") (pin "3") (pinfunction "P_3") (pintype "passive"))
      (node (ref "J413") (pin "3") (pinfunction "P_3") (pintype "passive"))
      (node (ref "J414") (pin "3") (pinfunction "P_3") (pintype "passive"))
      (node (ref "J415") (pin "3") (pinfunction "P_3") (pintype "passive"))
      (node (ref "J500") (pin "3") (pinfunction "P_3") (pintype "passive"))
      (node (ref "J501") (pin "3") (pinfunction "P_3") (pintype "passive"))
      (node (ref "J502") (pin "3") (pinfunction "P_3") (pintype "passive"))
      (node (ref "J503") (pin "3") (pinfunction "P_3") (pintype "passive"))
      (node (ref "J504") (pin "3") (pinfunction "P_3") (pintype "passive"))
      (node (ref "J505") (pin "3") (pinfunction "P_3") (pintype "passive"))
      (node (ref "J506") (pin "3") (pinfunction "P_3") (pintype "passive"))
      (node (ref "J507") (pin "3") (pinfunction "P_3") (pintype "passive"))
      (node (ref "J508") (pin "3") (pinfunction "P_3") (pintype "passive"))
      (node (ref "J509") (pin "3") (pinfunction "P_3") (pintype "passive"))
      (node (ref "J510") (pin "3") (pinfunction "P_3") (pintype "passive"))
      (node (ref "J511") (pin "3") (pinfunction "P_3") (pintype "passive"))
      (node (ref "J512") (pin "3") (pinfunction "P_3") (pintype "passive"))
      (node (ref "J513") (pin "3") (pinfunction "P_3") (pintype "passive"))
      (node (ref "J514") (pin "3") (pinfunction "P_3") (pintype "passive"))
      (node (ref "J515") (pin "3") (pinfunction "P_3") (pintype "passive"))
    )
  )
)
